# Half_Bridges.net
KiCad netlist of a schematic drawn in Altium Designer
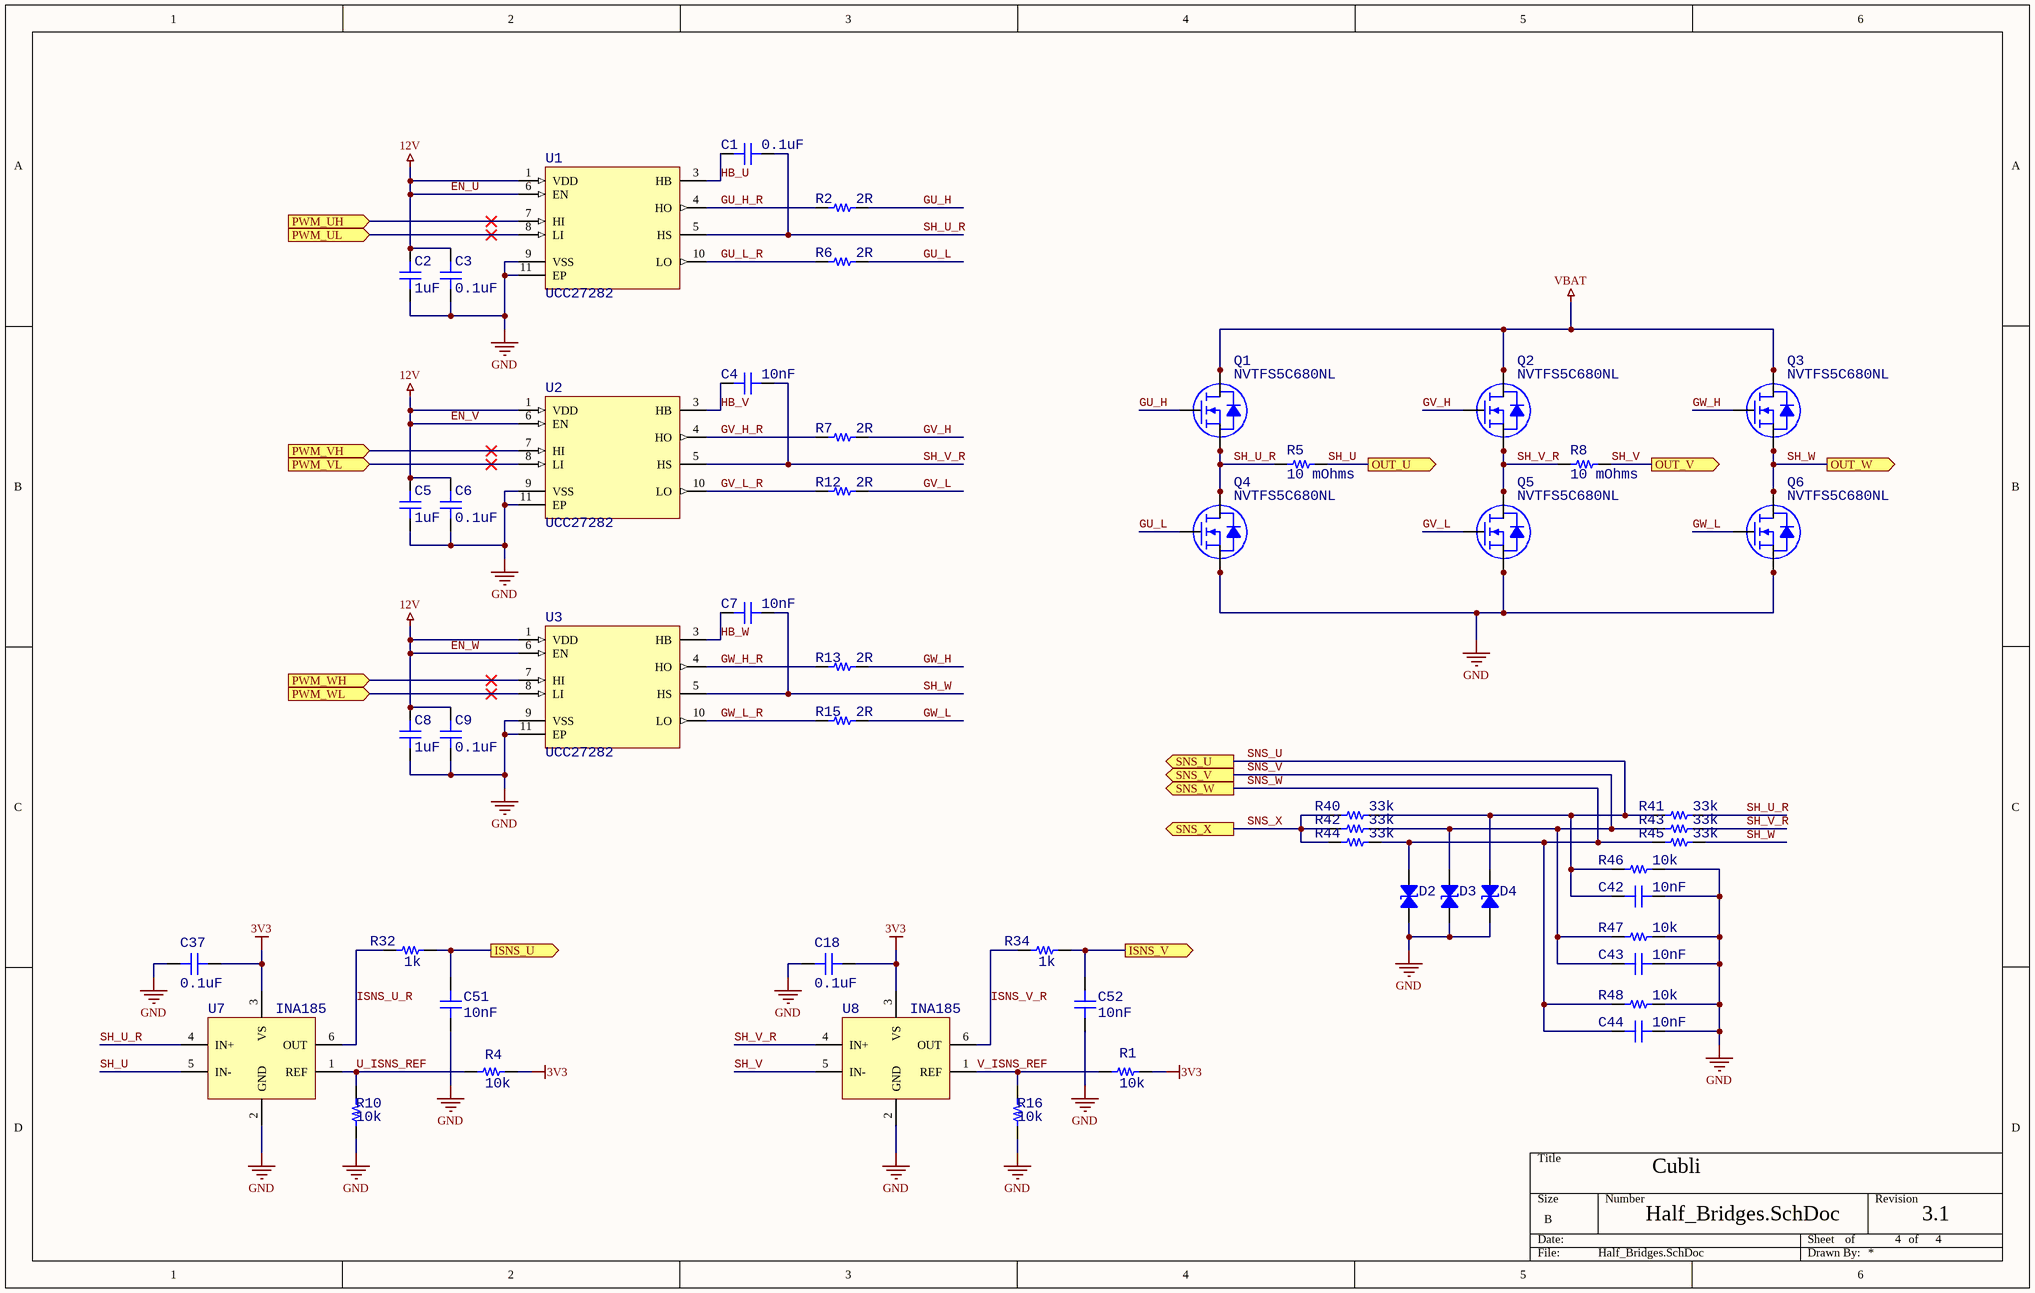
[diagram p0: Half_Bridges.SchDoc]

(export (version "E")
  (design (tool "Eeschema 10.0.6"))
  (components
    (comp (ref "C1")
      (value "0.1uF")
      (footprint "CAP_0402")
      (description "CAP CER 402")
      (libsource (lib "IC") (part "CAP_0402"))
    )
    (comp (ref "C2")
      (value "1uF")
      (footprint "CAP_0402")
      (description "CAP CER 402")
      (libsource (lib "IC") (part "CAP_0402"))
    )
    (comp (ref "C3")
      (value "0.1uF")
      (footprint "CAP_0402")
      (description "CAP CER 402")
      (libsource (lib "IC") (part "CAP_0402"))
    )
    (comp (ref "C4")
      (value "10nF")
      (footprint "CAP_0402")
      (description "CAP CER 402")
      (libsource (lib "IC") (part "CAP_0402"))
    )
    (comp (ref "C5")
      (value "1uF")
      (footprint "CAP_0402")
      (description "CAP CER 402")
      (libsource (lib "IC") (part "CAP_0402"))
    )
    (comp (ref "C6")
      (value "0.1uF")
      (footprint "CAP_0402")
      (description "CAP CER 402")
      (libsource (lib "IC") (part "CAP_0402"))
    )
    (comp (ref "C7")
      (value "10nF")
      (footprint "CAP_0402")
      (description "CAP CER 402")
      (libsource (lib "IC") (part "CAP_0402"))
    )
    (comp (ref "C8")
      (value "1uF")
      (footprint "CAP_0402")
      (description "CAP CER 402")
      (libsource (lib "IC") (part "CAP_0402"))
    )
    (comp (ref "C9")
      (value "0.1uF")
      (footprint "CAP_0402")
      (description "CAP CER 402")
      (libsource (lib "IC") (part "CAP_0402"))
    )
    (comp (ref "C18")
      (value "0.1uF")
      (footprint "CAP_0402")
      (description "CAP CER 402")
      (libsource (lib "IC") (part "CAP_0402"))
    )
    (comp (ref "C37")
      (value "0.1uF")
      (footprint "CAP_0402")
      (description "CAP CER 402")
      (libsource (lib "IC") (part "CAP_0402"))
    )
    (comp (ref "C42")
      (value "10nF")
      (footprint "CAP_0402")
      (description "CAP CER 402")
      (libsource (lib "IC") (part "CAP_0402"))
    )
    (comp (ref "C43")
      (value "10nF")
      (footprint "CAP_0402")
      (description "CAP CER 402")
      (libsource (lib "IC") (part "CAP_0402"))
    )
    (comp (ref "C44")
      (value "10nF")
      (footprint "CAP_0402")
      (description "CAP CER 402")
      (libsource (lib "IC") (part "CAP_0402"))
    )
    (comp (ref "C51")
      (value "10nF")
      (footprint "CAP_0402")
      (description "CAP CER 402")
      (libsource (lib "IC") (part "CAP_0402"))
    )
    (comp (ref "C52")
      (value "10nF")
      (footprint "CAP_0402")
      (description "CAP CER 402")
      (libsource (lib "IC") (part "CAP_0402"))
    )
    (comp (ref "D2")
      (value "TVN3V3B1S-DFN1006-2LDG")
      (footprint "0402")
      (description "TVS DIODE 3.3V 14.2PF DFN1006")
      (fields (field (name "MANUFACTURER") "INPAQ Technology Co., Ltd"))
      (libsource (lib "Celestial Altium Library - altium_library") (part "Diode TVS"))
    )
    (comp (ref "D3")
      (value "TVN3V3B1S-DFN1006-2LDG")
      (footprint "0402")
      (description "TVS DIODE 3.3V 14.2PF DFN1006")
      (fields (field (name "MANUFACTURER") "INPAQ Technology Co., Ltd"))
      (libsource (lib "Celestial Altium Library - altium_library") (part "Diode TVS"))
    )
    (comp (ref "D4")
      (value "TVN3V3B1S-DFN1006-2LDG")
      (footprint "0402")
      (description "TVS DIODE 3.3V 14.2PF DFN1006")
      (fields (field (name "MANUFACTURER") "INPAQ Technology Co., Ltd"))
      (libsource (lib "Celestial Altium Library - altium_library") (part "Diode TVS"))
    )
    (comp (ref "Q1")
      (value "NVTFS5C680NL")
      (footprint "NVTFS015N04CTAG")
      (description "N-FET")
      (libsource (lib "IC") (part "NVTFS5C680NL"))
    )
    (comp (ref "Q2")
      (value "NVTFS5C680NL")
      (footprint "NVTFS015N04CTAG")
      (description "N-FET")
      (libsource (lib "IC") (part "NVTFS5C680NL"))
    )
    (comp (ref "Q3")
      (value "NVTFS5C680NL")
      (footprint "NVTFS015N04CTAG")
      (description "N-FET")
      (libsource (lib "IC") (part "NVTFS5C680NL"))
    )
    (comp (ref "Q4")
      (value "NVTFS5C680NL")
      (footprint "NVTFS015N04CTAG")
      (description "N-FET")
      (libsource (lib "IC") (part "NVTFS5C680NL"))
    )
    (comp (ref "Q5")
      (value "NVTFS5C680NL")
      (footprint "NVTFS015N04CTAG")
      (description "N-FET")
      (libsource (lib "IC") (part "NVTFS5C680NL"))
    )
    (comp (ref "Q6")
      (value "NVTFS5C680NL")
      (footprint "NVTFS015N04CTAG")
      (description "N-FET")
      (libsource (lib "IC") (part "NVTFS5C680NL"))
    )
    (comp (ref "R1")
      (value "10k")
      (footprint "RES_0402")
      (description "RES 0402")
      (libsource (lib "IC") (part "RES_0402"))
    )
    (comp (ref "R2")
      (value "2R")
      (footprint "RES_0402")
      (description "RES 0402")
      (libsource (lib "IC") (part "RES_0402"))
    )
    (comp (ref "R4")
      (value "10k")
      (footprint "RES_0402")
      (description "RES 0402")
      (libsource (lib "IC") (part "RES_0402"))
    )
    (comp (ref "R5")
      (value "10 mOhms")
      (footprint "RES 1206_3216")
      (description "RES 0.039 OHM 1% 3/4W 1206")
      (fields (field (name "PART NUMBER") "KRL1632E-M-R039-F-T5") (field (name "MANUFACTURER") "Susumu"))
      (libsource (lib "Celestial Altium Library - altium_library") (part "Resistor"))
    )
    (comp (ref "R6")
      (value "2R")
      (footprint "RES_0402")
      (description "RES 0402")
      (libsource (lib "IC") (part "RES_0402"))
    )
    (comp (ref "R7")
      (value "2R")
      (footprint "RES_0402")
      (description "RES 0402")
      (libsource (lib "IC") (part "RES_0402"))
    )
    (comp (ref "R8")
      (value "10 mOhms")
      (footprint "RES 1206_3216")
      (description "RES 0.039 OHM 1% 3/4W 1206")
      (fields (field (name "PART NUMBER") "KRL1632E-M-R039-F-T5") (field (name "MANUFACTURER") "Susumu"))
      (libsource (lib "Celestial Altium Library - altium_library") (part "Resistor"))
    )
    (comp (ref "R10")
      (value "10k")
      (footprint "RES_0402")
      (description "RES 0402")
      (libsource (lib "IC") (part "RES_0402"))
    )
    (comp (ref "R12")
      (value "2R")
      (footprint "RES_0402")
      (description "RES 0402")
      (libsource (lib "IC") (part "RES_0402"))
    )
    (comp (ref "R13")
      (value "2R")
      (footprint "RES_0402")
      (description "RES 0402")
      (libsource (lib "IC") (part "RES_0402"))
    )
    (comp (ref "R15")
      (value "2R")
      (footprint "RES_0402")
      (description "RES 0402")
      (libsource (lib "IC") (part "RES_0402"))
    )
    (comp (ref "R16")
      (value "10k")
      (footprint "RES_0402")
      (description "RES 0402")
      (libsource (lib "IC") (part "RES_0402"))
    )
    (comp (ref "R32")
      (value "1k")
      (footprint "RES_0402")
      (description "RES 0402")
      (libsource (lib "IC") (part "RES_0402"))
    )
    (comp (ref "R34")
      (value "1k")
      (footprint "RES_0402")
      (description "RES 0402")
      (libsource (lib "IC") (part "RES_0402"))
    )
    (comp (ref "R40")
      (value "33k")
      (footprint "RES_0402")
      (description "RES 0402")
      (libsource (lib "IC") (part "RES_0402"))
    )
    (comp (ref "R41")
      (value "33k")
      (footprint "RES_0402")
      (description "RES 0402")
      (libsource (lib "IC") (part "RES_0402"))
    )
    (comp (ref "R42")
      (value "33k")
      (footprint "RES_0402")
      (description "RES 0402")
      (libsource (lib "IC") (part "RES_0402"))
    )
    (comp (ref "R43")
      (value "33k")
      (footprint "RES_0402")
      (description "RES 0402")
      (libsource (lib "IC") (part "RES_0402"))
    )
    (comp (ref "R44")
      (value "33k")
      (footprint "RES_0402")
      (description "RES 0402")
      (libsource (lib "IC") (part "RES_0402"))
    )
    (comp (ref "R45")
      (value "33k")
      (footprint "RES_0402")
      (description "RES 0402")
      (libsource (lib "IC") (part "RES_0402"))
    )
    (comp (ref "R46")
      (value "10k")
      (footprint "RES_0402")
      (description "RES 0402")
      (libsource (lib "IC") (part "RES_0402"))
    )
    (comp (ref "R47")
      (value "10k")
      (footprint "RES_0402")
      (description "RES 0402")
      (libsource (lib "IC") (part "RES_0402"))
    )
    (comp (ref "R48")
      (value "10k")
      (footprint "RES_0402")
      (description "RES 0402")
      (libsource (lib "IC") (part "RES_0402"))
    )
    (comp (ref "U1")
      (value "UCC27282")
      (footprint "VSON-10")
      (description "3-A, 120-V half bridge gate driver with 5-V UVLO, interlock and enable 10-VSON -40 to 125")
      (fields (field (name "MF") "Texas Instruments") (field (name "MP") "UCC27282DRCR"))
      (libsource (lib "IC") (part "UCC27282DRCR"))
    )
    (comp (ref "U2")
      (value "UCC27282")
      (footprint "VSON-10")
      (description "3-A, 120-V half bridge gate driver with 5-V UVLO, interlock and enable 10-VSON -40 to 125")
      (fields (field (name "MF") "Texas Instruments") (field (name "MP") "UCC27282DRCR"))
      (libsource (lib "IC") (part "UCC27282DRCR"))
    )
    (comp (ref "U3")
      (value "UCC27282")
      (footprint "VSON-10")
      (description "3-A, 120-V half bridge gate driver with 5-V UVLO, interlock and enable 10-VSON -40 to 125")
      (fields (field (name "MF") "Texas Instruments") (field (name "MP") "UCC27282DRCR"))
      (libsource (lib "IC") (part "UCC27282DRCR"))
    )
    (comp (ref "U7")
      (value "INA185")
      (footprint "TI SC70-6 DCK")
      (description "INA185A2")
      (libsource (lib "IC") (part "INA185"))
    )
    (comp (ref "U8")
      (value "INA185")
      (footprint "TI SC70-6 DCK")
      (description "INA185A2")
      (libsource (lib "IC") (part "INA185"))
    )
  )
  (nets
    (net (code "1") (name "/GU_H") (class "Default")
      (node (ref "Q1") (pin "4") (pinfunction "G_4") (pintype "passive"))
      (node (ref "R2") (pin "2") (pinfunction "2_2") (pintype "passive"))
    )
    (net (code "2") (name "/GU_H_R") (class "Default")
      (node (ref "R2") (pin "1") (pinfunction "1_1") (pintype "passive"))
      (node (ref "U1") (pin "4") (pinfunction "HO_4") (pintype "output"))
    )
    (net (code "3") (name "/GU_L") (class "Default")
      (node (ref "Q4") (pin "4") (pinfunction "G_4") (pintype "passive"))
      (node (ref "R6") (pin "2") (pinfunction "2_2") (pintype "passive"))
    )
    (net (code "4") (name "/GU_L_R") (class "Default")
      (node (ref "R6") (pin "1") (pinfunction "1_1") (pintype "passive"))
      (node (ref "U1") (pin "10") (pinfunction "LO_10") (pintype "output"))
    )
    (net (code "5") (name "/GV_H") (class "Default")
      (node (ref "Q2") (pin "4") (pinfunction "G_4") (pintype "passive"))
      (node (ref "R7") (pin "2") (pinfunction "2_2") (pintype "passive"))
    )
    (net (code "6") (name "/GV_H_R") (class "Default")
      (node (ref "R7") (pin "1") (pinfunction "1_1") (pintype "passive"))
      (node (ref "U2") (pin "4") (pinfunction "HO_4") (pintype "output"))
    )
    (net (code "7") (name "/GV_L") (class "Default")
      (node (ref "Q5") (pin "4") (pinfunction "G_4") (pintype "passive"))
      (node (ref "R12") (pin "2") (pinfunction "2_2") (pintype "passive"))
    )
    (net (code "8") (name "/GV_L_R") (class "Default")
      (node (ref "R12") (pin "1") (pinfunction "1_1") (pintype "passive"))
      (node (ref "U2") (pin "10") (pinfunction "LO_10") (pintype "output"))
    )
    (net (code "9") (name "/GW_H") (class "Default")
      (node (ref "Q3") (pin "4") (pinfunction "G_4") (pintype "passive"))
      (node (ref "R13") (pin "2") (pinfunction "2_2") (pintype "passive"))
    )
    (net (code "10") (name "/GW_H_R") (class "Default")
      (node (ref "R13") (pin "1") (pinfunction "1_1") (pintype "passive"))
      (node (ref "U3") (pin "4") (pinfunction "HO_4") (pintype "output"))
    )
    (net (code "11") (name "/GW_L") (class "Default")
      (node (ref "Q6") (pin "4") (pinfunction "G_4") (pintype "passive"))
      (node (ref "R15") (pin "2") (pinfunction "2_2") (pintype "passive"))
    )
    (net (code "12") (name "/GW_L_R") (class "Default")
      (node (ref "R15") (pin "1") (pinfunction "1_1") (pintype "passive"))
      (node (ref "U3") (pin "10") (pinfunction "LO_10") (pintype "output"))
    )
    (net (code "13") (name "/HB_U") (class "Default")
      (node (ref "C1") (pin "2") (pinfunction "2_2") (pintype "passive"))
      (node (ref "U1") (pin "3") (pinfunction "HB_3") (pintype "power_in"))
    )
    (net (code "14") (name "/HB_V") (class "Default")
      (node (ref "C4") (pin "2") (pinfunction "2_2") (pintype "passive"))
      (node (ref "U2") (pin "3") (pinfunction "HB_3") (pintype "power_in"))
    )
    (net (code "15") (name "/HB_W") (class "Default")
      (node (ref "C7") (pin "2") (pinfunction "2_2") (pintype "passive"))
      (node (ref "U3") (pin "3") (pinfunction "HB_3") (pintype "power_in"))
    )
    (net (code "16") (name "/ISNS_U") (class "Default")
      (node (ref "C51") (pin "1") (pinfunction "1_1") (pintype "passive"))
      (node (ref "R32") (pin "1") (pinfunction "1_1") (pintype "passive"))
    )
    (net (code "17") (name "/ISNS_U_R") (class "Default")
      (node (ref "R32") (pin "2") (pinfunction "2_2") (pintype "passive"))
      (node (ref "U7") (pin "6") (pinfunction "OUT_6") (pintype "passive"))
    )
    (net (code "18") (name "/ISNS_V") (class "Default")
      (node (ref "C52") (pin "1") (pinfunction "1_1") (pintype "passive"))
      (node (ref "R34") (pin "1") (pinfunction "1_1") (pintype "passive"))
    )
    (net (code "19") (name "/ISNS_V_R") (class "Default")
      (node (ref "R34") (pin "2") (pinfunction "2_2") (pintype "passive"))
      (node (ref "U8") (pin "6") (pinfunction "OUT_6") (pintype "passive"))
    )
    (net (code "20") (name "/PWM_UH") (class "Default")
      (node (ref "U1") (pin "7") (pinfunction "HI_7") (pintype "input"))
    )
    (net (code "21") (name "/PWM_UL") (class "Default")
      (node (ref "U1") (pin "8") (pinfunction "LI_8") (pintype "input"))
    )
    (net (code "22") (name "/PWM_VH") (class "Default")
      (node (ref "U2") (pin "7") (pinfunction "HI_7") (pintype "input"))
    )
    (net (code "23") (name "/PWM_VL") (class "Default")
      (node (ref "U2") (pin "8") (pinfunction "LI_8") (pintype "input"))
    )
    (net (code "24") (name "/PWM_WH") (class "Default")
      (node (ref "U3") (pin "7") (pinfunction "HI_7") (pintype "input"))
    )
    (net (code "25") (name "/PWM_WL") (class "Default")
      (node (ref "U3") (pin "8") (pinfunction "LI_8") (pintype "input"))
    )
    (net (code "26") (name "/SH_U") (class "Default")
      (node (ref "R5") (pin "2") (pinfunction "2_2") (pintype "passive"))
      (node (ref "U7") (pin "5") (pinfunction "IN-_5") (pintype "passive"))
    )
    (net (code "27") (name "/SH_U_R") (class "Default")
      (node (ref "C1") (pin "1") (pinfunction "1_1") (pintype "passive"))
      (node (ref "Q1") (pin "1") (pinfunction "S_1") (pintype "passive"))
      (node (ref "Q1") (pin "2") (pinfunction "S_2") (pintype "passive"))
      (node (ref "Q1") (pin "3") (pinfunction "S_3") (pintype "passive"))
      (node (ref "Q4") (pin "5") (pinfunction "D_5") (pintype "passive"))
      (node (ref "Q4") (pin "6") (pinfunction "D_6") (pintype "passive"))
      (node (ref "Q4") (pin "7") (pinfunction "D_7") (pintype "passive"))
      (node (ref "Q4") (pin "8") (pinfunction "D_8") (pintype "passive"))
      (node (ref "R41") (pin "1") (pinfunction "1_1") (pintype "passive"))
      (node (ref "R5") (pin "1") (pinfunction "1_1") (pintype "passive"))
      (node (ref "U1") (pin "5") (pinfunction "HS_5") (pintype "power_in"))
      (node (ref "U7") (pin "4") (pinfunction "IN+_4") (pintype "passive"))
    )
    (net (code "28") (name "/SH_V") (class "Default")
      (node (ref "R8") (pin "2") (pinfunction "2_2") (pintype "passive"))
      (node (ref "U8") (pin "5") (pinfunction "IN-_5") (pintype "passive"))
    )
    (net (code "29") (name "/SH_V_R") (class "Default")
      (node (ref "C4") (pin "1") (pinfunction "1_1") (pintype "passive"))
      (node (ref "Q2") (pin "1") (pinfunction "S_1") (pintype "passive"))
      (node (ref "Q2") (pin "2") (pinfunction "S_2") (pintype "passive"))
      (node (ref "Q2") (pin "3") (pinfunction "S_3") (pintype "passive"))
      (node (ref "Q5") (pin "5") (pinfunction "D_5") (pintype "passive"))
      (node (ref "Q5") (pin "6") (pinfunction "D_6") (pintype "passive"))
      (node (ref "Q5") (pin "7") (pinfunction "D_7") (pintype "passive"))
      (node (ref "Q5") (pin "8") (pinfunction "D_8") (pintype "passive"))
      (node (ref "R43") (pin "1") (pinfunction "1_1") (pintype "passive"))
      (node (ref "R8") (pin "1") (pinfunction "1_1") (pintype "passive"))
      (node (ref "U2") (pin "5") (pinfunction "HS_5") (pintype "power_in"))
      (node (ref "U8") (pin "4") (pinfunction "IN+_4") (pintype "passive"))
    )
    (net (code "30") (name "/SH_W") (class "Default")
      (node (ref "C7") (pin "1") (pinfunction "1_1") (pintype "passive"))
      (node (ref "Q3") (pin "1") (pinfunction "S_1") (pintype "passive"))
      (node (ref "Q3") (pin "2") (pinfunction "S_2") (pintype "passive"))
      (node (ref "Q3") (pin "3") (pinfunction "S_3") (pintype "passive"))
      (node (ref "Q6") (pin "5") (pinfunction "D_5") (pintype "passive"))
      (node (ref "Q6") (pin "6") (pinfunction "D_6") (pintype "passive"))
      (node (ref "Q6") (pin "7") (pinfunction "D_7") (pintype "passive"))
      (node (ref "Q6") (pin "8") (pinfunction "D_8") (pintype "passive"))
      (node (ref "R45") (pin "1") (pinfunction "1_1") (pintype "passive"))
      (node (ref "U3") (pin "5") (pinfunction "HS_5") (pintype "power_in"))
    )
    (net (code "31") (name "/SNS_U") (class "Default")
      (node (ref "C42") (pin "2") (pinfunction "2_2") (pintype "passive"))
      (node (ref "D4") (pin "2") (pinfunction "2_2") (pintype "passive"))
      (node (ref "R40") (pin "1") (pinfunction "1_1") (pintype "passive"))
      (node (ref "R41") (pin "2") (pinfunction "2_2") (pintype "passive"))
      (node (ref "R46") (pin "1") (pinfunction "1_1") (pintype "passive"))
    )
    (net (code "32") (name "/SNS_V") (class "Default")
      (node (ref "C43") (pin "2") (pinfunction "2_2") (pintype "passive"))
      (node (ref "D3") (pin "2") (pinfunction "2_2") (pintype "passive"))
      (node (ref "R42") (pin "1") (pinfunction "1_1") (pintype "passive"))
      (node (ref "R43") (pin "2") (pinfunction "2_2") (pintype "passive"))
      (node (ref "R47") (pin "1") (pinfunction "1_1") (pintype "passive"))
    )
    (net (code "33") (name "/SNS_W") (class "Default")
      (node (ref "C44") (pin "2") (pinfunction "2_2") (pintype "passive"))
      (node (ref "D2") (pin "2") (pinfunction "2_2") (pintype "passive"))
      (node (ref "R44") (pin "1") (pinfunction "1_1") (pintype "passive"))
      (node (ref "R45") (pin "2") (pinfunction "2_2") (pintype "passive"))
      (node (ref "R48") (pin "1") (pinfunction "1_1") (pintype "passive"))
    )
    (net (code "34") (name "/SNS_X") (class "Default")
      (node (ref "R40") (pin "2") (pinfunction "2_2") (pintype "passive"))
      (node (ref "R42") (pin "2") (pinfunction "2_2") (pintype "passive"))
      (node (ref "R44") (pin "2") (pinfunction "2_2") (pintype "passive"))
    )
    (net (code "35") (name "/U_ISNS_REF") (class "Default")
      (node (ref "R10") (pin "1") (pinfunction "1_1") (pintype "passive"))
      (node (ref "R4") (pin "2") (pinfunction "2_2") (pintype "passive"))
      (node (ref "U7") (pin "1") (pinfunction "REF_1") (pintype "passive"))
    )
    (net (code "36") (name "/V_ISNS_REF") (class "Default")
      (node (ref "R1") (pin "2") (pinfunction "2_2") (pintype "passive"))
      (node (ref "R16") (pin "1") (pinfunction "1_1") (pintype "passive"))
      (node (ref "U8") (pin "1") (pinfunction "REF_1") (pintype "passive"))
    )
    (net (code "37") (name "3V3") (class "Default")
      (node (ref "C18") (pin "1") (pinfunction "1_1") (pintype "passive"))
      (node (ref "C37") (pin "1") (pinfunction "1_1") (pintype "passive"))
      (node (ref "R1") (pin "1") (pinfunction "1_1") (pintype "passive"))
      (node (ref "R4") (pin "1") (pinfunction "1_1") (pintype "passive"))
      (node (ref "U7") (pin "3") (pinfunction "VS_3") (pintype "passive"))
      (node (ref "U8") (pin "3") (pinfunction "VS_3") (pintype "passive"))
    )
    (net (code "38") (name "12V") (class "Default")
      (node (ref "C2") (pin "1") (pinfunction "1_1") (pintype "passive"))
      (node (ref "C3") (pin "1") (pinfunction "1_1") (pintype "passive"))
      (node (ref "C5") (pin "1") (pinfunction "1_1") (pintype "passive"))
      (node (ref "C6") (pin "1") (pinfunction "1_1") (pintype "passive"))
      (node (ref "C8") (pin "1") (pinfunction "1_1") (pintype "passive"))
      (node (ref "C9") (pin "1") (pinfunction "1_1") (pintype "passive"))
      (node (ref "U1") (pin "1") (pinfunction "VDD_1") (pintype "input"))
      (node (ref "U1") (pin "6") (pinfunction "EN_6") (pintype "input"))
      (node (ref "U2") (pin "1") (pinfunction "VDD_1") (pintype "input"))
      (node (ref "U2") (pin "6") (pinfunction "EN_6") (pintype "input"))
      (node (ref "U3") (pin "1") (pinfunction "VDD_1") (pintype "input"))
      (node (ref "U3") (pin "6") (pinfunction "EN_6") (pintype "input"))
    )
    (net (code "39") (name "GND") (class "Default")
      (node (ref "C18") (pin "2") (pinfunction "2_2") (pintype "passive"))
      (node (ref "C2") (pin "2") (pinfunction "2_2") (pintype "passive"))
      (node (ref "C3") (pin "2") (pinfunction "2_2") (pintype "passive"))
      (node (ref "C37") (pin "2") (pinfunction "2_2") (pintype "passive"))
      (node (ref "C42") (pin "1") (pinfunction "1_1") (pintype "passive"))
      (node (ref "C43") (pin "1") (pinfunction "1_1") (pintype "passive"))
      (node (ref "C44") (pin "1") (pinfunction "1_1") (pintype "passive"))
      (node (ref "C5") (pin "2") (pinfunction "2_2") (pintype "passive"))
      (node (ref "C51") (pin "2") (pinfunction "2_2") (pintype "passive"))
      (node (ref "C52") (pin "2") (pinfunction "2_2") (pintype "passive"))
      (node (ref "C6") (pin "2") (pinfunction "2_2") (pintype "passive"))
      (node (ref "C8") (pin "2") (pinfunction "2_2") (pintype "passive"))
      (node (ref "C9") (pin "2") (pinfunction "2_2") (pintype "passive"))
      (node (ref "D2") (pin "1") (pinfunction "1_1") (pintype "passive"))
      (node (ref "D3") (pin "1") (pinfunction "1_1") (pintype "passive"))
      (node (ref "D4") (pin "1") (pinfunction "1_1") (pintype "passive"))
      (node (ref "Q4") (pin "1") (pinfunction "S_1") (pintype "passive"))
      (node (ref "Q4") (pin "2") (pinfunction "S_2") (pintype "passive"))
      (node (ref "Q4") (pin "3") (pinfunction "S_3") (pintype "passive"))
      (node (ref "Q5") (pin "1") (pinfunction "S_1") (pintype "passive"))
      (node (ref "Q5") (pin "2") (pinfunction "S_2") (pintype "passive"))
      (node (ref "Q5") (pin "3") (pinfunction "S_3") (pintype "passive"))
      (node (ref "Q6") (pin "1") (pinfunction "S_1") (pintype "passive"))
      (node (ref "Q6") (pin "2") (pinfunction "S_2") (pintype "passive"))
      (node (ref "Q6") (pin "3") (pinfunction "S_3") (pintype "passive"))
      (node (ref "R10") (pin "2") (pinfunction "2_2") (pintype "passive"))
      (node (ref "R16") (pin "2") (pinfunction "2_2") (pintype "passive"))
      (node (ref "R46") (pin "2") (pinfunction "2_2") (pintype "passive"))
      (node (ref "R47") (pin "2") (pinfunction "2_2") (pintype "passive"))
      (node (ref "R48") (pin "2") (pinfunction "2_2") (pintype "passive"))
      (node (ref "U1") (pin "11") (pinfunction "EP_11") (pintype "passive"))
      (node (ref "U1") (pin "9") (pinfunction "VSS_9") (pintype "power_in"))
      (node (ref "U2") (pin "11") (pinfunction "EP_11") (pintype "passive"))
      (node (ref "U2") (pin "9") (pinfunction "VSS_9") (pintype "power_in"))
      (node (ref "U3") (pin "11") (pinfunction "EP_11") (pintype "passive"))
      (node (ref "U3") (pin "9") (pinfunction "VSS_9") (pintype "power_in"))
      (node (ref "U7") (pin "2") (pinfunction "GND_2") (pintype "passive"))
      (node (ref "U8") (pin "2") (pinfunction "GND_2") (pintype "passive"))
    )
    (net (code "40") (name "VBAT") (class "Default")
      (node (ref "Q1") (pin "5") (pinfunction "D_5") (pintype "passive"))
      (node (ref "Q1") (pin "6") (pinfunction "D_6") (pintype "passive"))
      (node (ref "Q1") (pin "7") (pinfunction "D_7") (pintype "passive"))
      (node (ref "Q1") (pin "8") (pinfunction "D_8") (pintype "passive"))
      (node (ref "Q2") (pin "5") (pinfunction "D_5") (pintype "passive"))
      (node (ref "Q2") (pin "6") (pinfunction "D_6") (pintype "passive"))
      (node (ref "Q2") (pin "7") (pinfunction "D_7") (pintype "passive"))
      (node (ref "Q2") (pin "8") (pinfunction "D_8") (pintype "passive"))
      (node (ref "Q3") (pin "5") (pinfunction "D_5") (pintype "passive"))
      (node (ref "Q3") (pin "6") (pinfunction "D_6") (pintype "passive"))
      (node (ref "Q3") (pin "7") (pinfunction "D_7") (pintype "passive"))
      (node (ref "Q3") (pin "8") (pinfunction "D_8") (pintype "passive"))
    )
  )
)
